# LED_POWER_2.net
KiCad netlist of a schematic drawn in Altium Designer
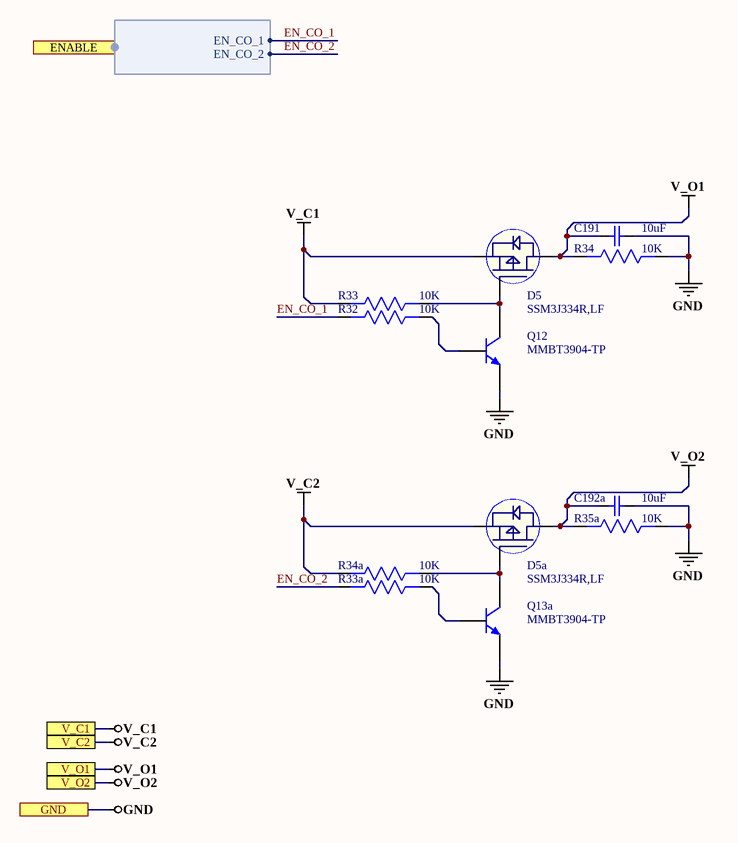
[diagram p0: LED_POWER 2.SchDoc]

(export (version "E")
  (design (tool "Eeschema 10.0.6"))
  (components
    (comp (ref "C191")
      (value "10uF")
      (footprint "Cap0603")
      (description "CAP CER 10UF 25V X5R 0603")
      (fields
        (field (name "MANUFACTURER") "Murata")
        (field (name "MANUFACTURER PART NUMBER") "GRM188R61E106KA73D")
      )
      (libsource (lib "TT_IntLib") (part "GRM188R61E106KA73D"))
    )
    (comp (ref "C192a")
      (value "10uF")
      (footprint "Cap0603")
      (description "CAP CER 10UF 25V X5R 0603")
      (fields
        (field (name "MANUFACTURER") "Murata")
        (field (name "MANUFACTURER PART NUMBER") "GRM188R61E106KA73D")
      )
      (libsource (lib "TT_IntLib") (part "GRM188R61E106KA73D"))
    )
    (comp (ref "D5")
      (value "SSM3J334R,LF")
      (footprint "SOT-23F")
      (description "MOSFET P-CH 30V 4A SOT23F")
      (fields (field (name "MANUFACTURER") "Toshiba"))
      (libsource (lib "TT_IntLib") (part "SSM3J334R,LF"))
    )
    (comp (ref "D5a")
      (value "SSM3J334R,LF")
      (footprint "SOT-23F")
      (description "MOSFET P-CH 30V 4A SOT23F")
      (fields (field (name "MANUFACTURER") "Toshiba"))
      (libsource (lib "TT_IntLib") (part "SSM3J334R,LF"))
    )
    (comp (ref "Q12")
      (value "MMBT3904-TP")
      (footprint "SOT-23F")
      (description "TRANS NPN 40V 0.2A SOT23")
      (fields (field (name "MANUFACTURER") "MCC"))
      (libsource (lib "TT_IntLib") (part "MMBT3904-TP"))
    )
    (comp (ref "Q13a")
      (value "MMBT3904-TP")
      (footprint "SOT-23F")
      (description "TRANS NPN 40V 0.2A SOT23")
      (fields (field (name "MANUFACTURER") "MCC"))
      (libsource (lib "TT_IntLib") (part "MMBT3904-TP"))
    )
    (comp (ref "R32")
      (value "10K")
      (footprint "Res-0201")
      (description "GENERAL 0201 11% REEL (7INCH)")
      (fields
        (field (name "MANUFACTURER") "Yageo")
        (field (name "MANUFACTURER PART NUMBER") "RC0201FR-0710KL")
      )
      (libsource (lib "TT_IntLib") (part "RC0201FR-0710KL"))
    )
    (comp (ref "R33")
      (value "10K")
      (footprint "Res-0201")
      (description "GENERAL 0201 11% REEL (7INCH)")
      (fields
        (field (name "MANUFACTURER") "Yageo")
        (field (name "MANUFACTURER PART NUMBER") "RC0201FR-0710KL")
      )
      (libsource (lib "TT_IntLib") (part "RC0201FR-0710KL"))
    )
    (comp (ref "R33a")
      (value "10K")
      (footprint "Res-0201")
      (description "GENERAL 0201 11% REEL (7INCH)")
      (fields
        (field (name "MANUFACTURER") "Yageo")
        (field (name "MANUFACTURER PART NUMBER") "RC0201FR-0710KL")
      )
      (libsource (lib "TT_IntLib") (part "RC0201FR-0710KL"))
    )
    (comp (ref "R34")
      (value "10K")
      (footprint "Res-0201")
      (description "GENERAL 0201 11% REEL (7INCH)")
      (fields
        (field (name "MANUFACTURER") "Yageo")
        (field (name "MANUFACTURER PART NUMBER") "RC0201FR-0710KL")
      )
      (libsource (lib "TT_IntLib") (part "RC0201FR-0710KL"))
    )
    (comp (ref "R34a")
      (value "10K")
      (footprint "Res-0201")
      (description "GENERAL 0201 11% REEL (7INCH)")
      (fields
        (field (name "MANUFACTURER") "Yageo")
        (field (name "MANUFACTURER PART NUMBER") "RC0201FR-0710KL")
      )
      (libsource (lib "TT_IntLib") (part "RC0201FR-0710KL"))
    )
    (comp (ref "R35a")
      (value "10K")
      (footprint "Res-0201")
      (description "GENERAL 0201 11% REEL (7INCH)")
      (fields
        (field (name "MANUFACTURER") "Yageo")
        (field (name "MANUFACTURER PART NUMBER") "RC0201FR-0710KL")
      )
      (libsource (lib "TT_IntLib") (part "RC0201FR-0710KL"))
    )
  )
  (nets
    (net (code "2") (name "/EN_CO_1") (class "Default") (node (ref "R32") (pin "2") (pintype "passive")))
    (net (code "3") (name "/EN_CO_2") (class "Default") (node (ref "R33a") (pin "2") (pintype "passive")))
    (net (code "5") (name "GND") (class "Default")
      (node (ref "C191") (pin "1") (pintype "passive"))
      (node (ref "C192a") (pin "1") (pintype "passive"))
      (node (ref "Q12") (pin "2") (pinfunction "E_2") (pintype "passive"))
      (node (ref "Q13a") (pin "2") (pinfunction "E_2") (pintype "passive"))
      (node (ref "R34") (pin "1") (pintype "passive"))
      (node (ref "R35a") (pin "1") (pintype "passive"))
    )
    (net (code "6") (name "Net-(D5-G)") (class "Default")
      (node (ref "D5") (pin "1") (pinfunction "G_1") (pintype "passive"))
      (node (ref "Q12") (pin "3") (pinfunction "C_3") (pintype "passive"))
      (node (ref "R33") (pin "1") (pintype "passive"))
    )
    (net (code "7") (name "Net-(D5a-G)") (class "Default")
      (node (ref "D5a") (pin "1") (pinfunction "G_1") (pintype "passive"))
      (node (ref "Q13a") (pin "3") (pinfunction "C_3") (pintype "passive"))
      (node (ref "R34a") (pin "1") (pintype "passive"))
    )
    (net (code "8") (name "Net-(Q12-B)") (class "Default")
      (node (ref "Q12") (pin "1") (pinfunction "B_1") (pintype "passive"))
      (node (ref "R32") (pin "1") (pintype "passive"))
    )
    (net (code "9") (name "Net-(Q13a-B)") (class "Default")
      (node (ref "Q13a") (pin "1") (pinfunction "B_1") (pintype "passive"))
      (node (ref "R33a") (pin "1") (pintype "passive"))
    )
    (net (code "10") (name "V_C1") (class "Default")
      (node (ref "D5") (pin "2") (pinfunction "S_2") (pintype "passive"))
      (node (ref "R33") (pin "2") (pintype "passive"))
    )
    (net (code "11") (name "V_C2") (class "Default")
      (node (ref "D5a") (pin "2") (pinfunction "S_2") (pintype "passive"))
      (node (ref "R34a") (pin "2") (pintype "passive"))
    )
    (net (code "12") (name "V_O1") (class "Default")
      (node (ref "C191") (pin "2") (pintype "passive"))
      (node (ref "D5") (pin "3") (pinfunction "D_3") (pintype "passive"))
      (node (ref "R34") (pin "2") (pintype "passive"))
    )
    (net (code "13") (name "V_O2") (class "Default")
      (node (ref "C192a") (pin "2") (pintype "passive"))
      (node (ref "D5a") (pin "3") (pinfunction "D_3") (pintype "passive"))
      (node (ref "R35a") (pin "2") (pintype "passive"))
    )
  )
)
